# AT_Guard_Simple_Power.net
KiCad netlist of a schematic drawn in Altium Designer
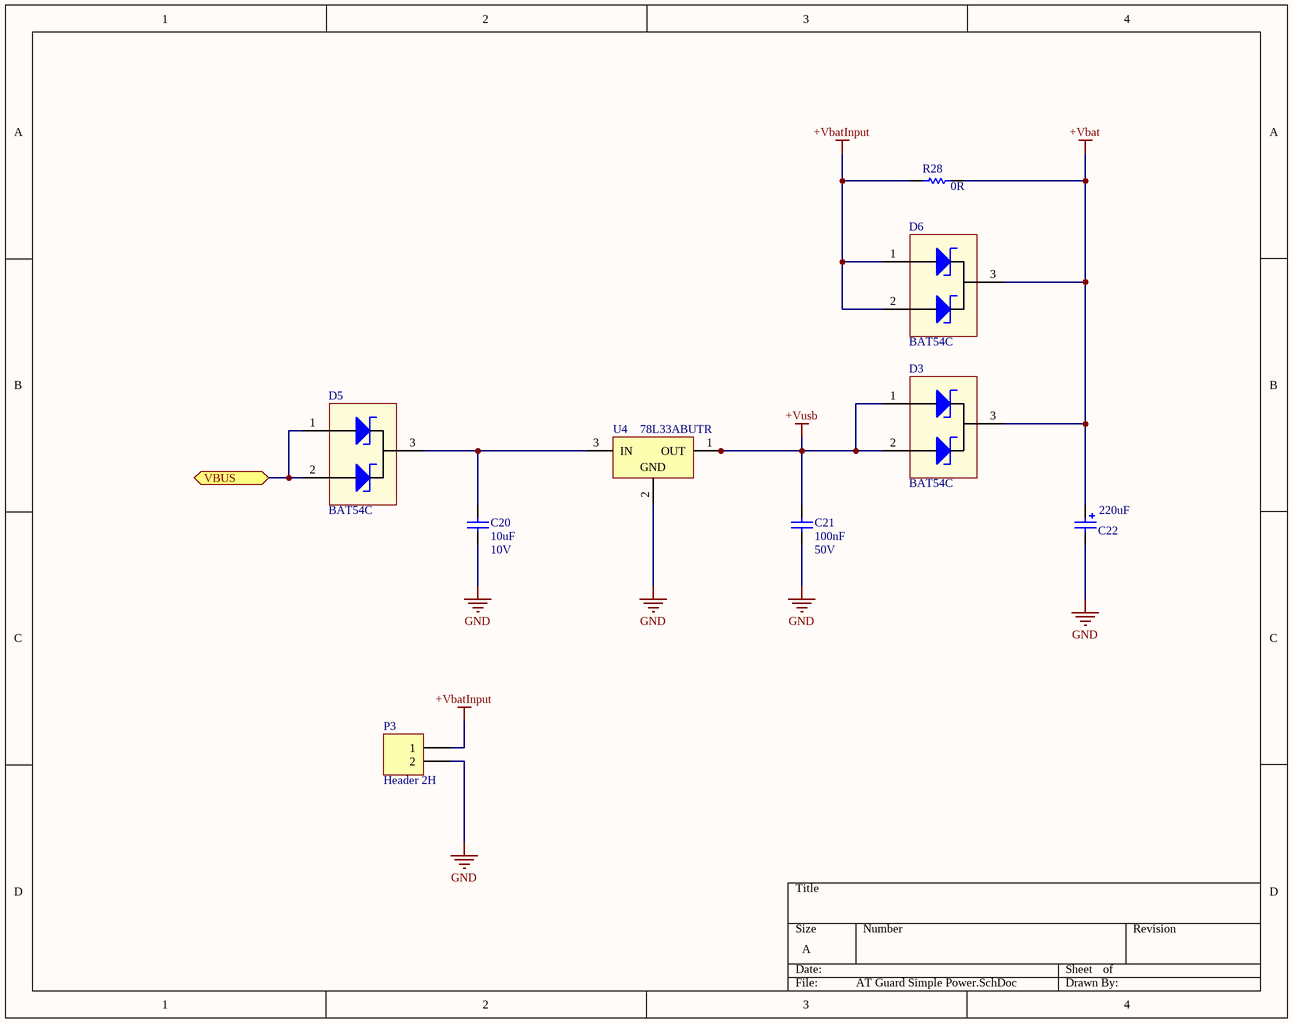
[diagram p0: AT Guard Simple Power.SchDoc]

(export (version "E")
  (design (tool "Eeschema 10.0.6"))
  (components
    (comp (ref "C20")
      (value "10uF")
      (footprint "3-0603_L")
      (description "Capacitor")
      (fields
        (field (name "VOLTAGE") "10V")
        (field (name "Comment") "Cap")
        (field (name "PUBLISHER") "Altium Limited")
      )
      (libsource (lib "Erdem_05112012") (part "Cap"))
    )
    (comp (ref "C21")
      (value "100nF")
      (footprint "3-0603_L")
      (description "Capacitor")
      (fields
        (field (name "VOLTAGE") "50V")
        (field (name "Comment") "Cap")
        (field (name "PUBLISHER") "Altium Limited")
      )
      (libsource (lib "Erdem_05112012") (part "Cap"))
    )
    (comp (ref "C22")
      (value "220uF")
      (footprint "C")
      (fields
        (field (name "VOLTAGE") "6.3V")
        (field (name "Comment") "CAP-Tantal")
        (field (name "PUBLISHER") "Altium Limited")
      )
      (libsource (lib "Erdem_05112012") (part "CAP-Tantal"))
    )
    (comp (ref "D3")
      (value "BAT54C")
      (footprint "SOT23_N")
      (description "2x200 mA Shottky Rectifier")
      (fields (field (name "PUBLISHER") "Altium Limited"))
      (libsource (lib "Erdem_05112012") (part "BAT54C"))
    )
    (comp (ref "D5")
      (value "BAT54C")
      (footprint "SOT23_N")
      (description "2x200 mA Shottky Rectifier")
      (fields (field (name "PUBLISHER") "Altium Limited"))
      (libsource (lib "Erdem_05112012") (part "BAT54C"))
    )
    (comp (ref "D6")
      (value "BAT54C")
      (footprint "SOT23_N")
      (description "2x200 mA Shottky Rectifier")
      (fields (field (name "PUBLISHER") "Altium Limited"))
      (libsource (lib "Erdem_05112012") (part "BAT54C"))
    )
    (comp (ref "P3")
      (value "Header 2H")
      (footprint "HDR1X2H-180 derece")
      (description "Header, 2-Pin, Right Angle")
      (fields (field (name "PUBLISHER") "Altium Limited"))
      (libsource (lib "Erdem_05112012") (part "Header 2H"))
    )
    (comp (ref "R28")
      (value "0R")
      (footprint "6-0805_N")
      (description "Resistor")
      (fields (field (name "Comment") "Res1") (field (name "PUBLISHER") "Altium Limited"))
      (libsource (lib "Erdem_05112012") (part "Res1"))
    )
    (comp (ref "U4")
      (value "78L33ABUTR")
      (footprint "SOT89M")
      (description "Precision 500mA Regulator")
      (fields (field (name "PUBLISHER") "Altium Limited"))
      (libsource (lib "Erdem_05112012") (part "78L33ABUTR"))
    )
  )
  (nets
    (net (code "1") (name "+Vbat") (class "Default")
      (node (ref "C22") (pin "1") (pinfunction "1_1") (pintype "passive"))
      (node (ref "D3") (pin "3") (pinfunction "A_3") (pintype "passive"))
      (node (ref "D6") (pin "3") (pinfunction "A_3") (pintype "passive"))
      (node (ref "R28") (pin "2") (pinfunction "2_2") (pintype "passive"))
    )
    (net (code "2") (name "+VbatInput") (class "Default")
      (node (ref "D6") (pin "1") (pinfunction "K1_1") (pintype "passive"))
      (node (ref "D6") (pin "2") (pinfunction "K2_2") (pintype "passive"))
      (node (ref "P3") (pin "1") (pinfunction "1_1") (pintype "passive"))
      (node (ref "R28") (pin "1") (pinfunction "1_1") (pintype "passive"))
    )
    (net (code "3") (name "+Vusb") (class "Default")
      (node (ref "C21") (pin "2") (pinfunction "2_2") (pintype "passive"))
      (node (ref "D3") (pin "1") (pinfunction "K1_1") (pintype "passive"))
      (node (ref "D3") (pin "2") (pinfunction "K2_2") (pintype "passive"))
      (node (ref "U4") (pin "1") (pinfunction "OUT_1") (pintype "power_in"))
    )
    (net (code "4") (name "/VBUS") (class "Default")
      (node (ref "D5") (pin "1") (pinfunction "K1_1") (pintype "passive"))
      (node (ref "D5") (pin "2") (pinfunction "K2_2") (pintype "passive"))
    )
    (net (code "5") (name "GND") (class "Default")
      (node (ref "C20") (pin "1") (pinfunction "1_1") (pintype "passive"))
      (node (ref "C21") (pin "1") (pinfunction "1_1") (pintype "passive"))
      (node (ref "C22") (pin "2") (pinfunction "2_2") (pintype "passive"))
      (node (ref "P3") (pin "2") (pinfunction "2_2") (pintype "passive"))
      (node (ref "U4") (pin "2") (pinfunction "GND_2") (pintype "power_in"))
    )
    (net (code "6") (name "Net-(D5-A)") (class "Default")
      (node (ref "C20") (pin "2") (pinfunction "2_2") (pintype "passive"))
      (node (ref "D5") (pin "3") (pinfunction "A_3") (pintype "passive"))
      (node (ref "U4") (pin "3") (pinfunction "IN_3") (pintype "power_in"))
    )
  )
)
